# RxFrontendWaveyRadar.net
KiCad netlist of a schematic drawn in Altium Designer
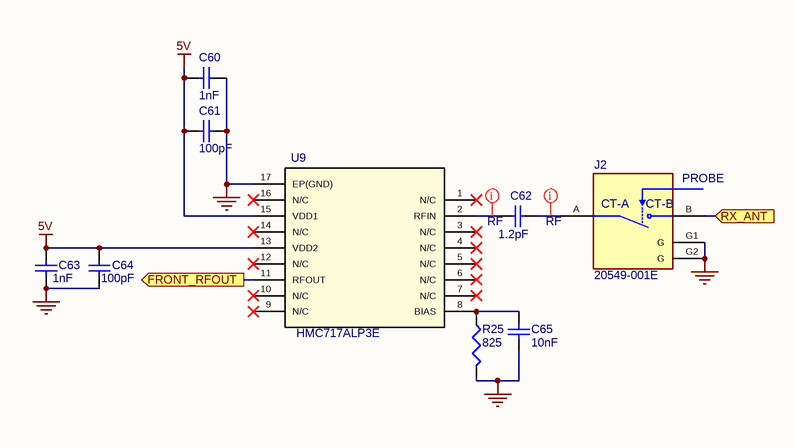
[diagram p0: RxFrontendWaveyRadar.SchDoc]

(export (version "E")
  (design (tool "Eeschema 10.0.6"))
  (components
    (comp (ref "C60")
      (value "1nF")
      (footprint "CAPC0402(1005)33_L")
      (description "Chip Capacitor, 1nF +/-20%, 50V, 0402, Thickness 0.33 mm")
      (fields (field (name "TOLERANCE") "10%") (field (name "Comment") "Capacitor 1nF +/-20% 50V 0402"))
      (libsource (lib "University of South Florida") (part "CAP-NP-2"))
    )
    (comp (ref "C61")
      (value "100pF")
      (footprint "CAPC1005X56X25LL10T15")
      (fields (field (name "Comment") "04023A101JAT2A"))
      (libsource (lib "University of South Florida") (part "CAP-NP-2"))
    )
    (comp (ref "C62")
      (value "1.2pF")
      (footprint "FP-C0402-BB-MFG")
      (description "Cap Ceramic 1.2pF 50V C0G 0.25pF SMD 0402 125°C Paper T/R")
      (fields (field (name "Comment") "C0402C129C5GACTU"))
      (libsource (lib "University of South Florida") (part "CAP-NP-2"))
    )
    (comp (ref "C63")
      (value "1nF")
      (footprint "CAPC0402(1005)33_L")
      (description "Chip Capacitor, 1nF +/-20%, 50V, 0402, Thickness 0.33 mm")
      (fields (field (name "TOLERANCE") "10%") (field (name "Comment") "Capacitor 1nF +/-20% 50V 0402"))
      (libsource (lib "University of South Florida") (part "CAP-NP-2"))
    )
    (comp (ref "C64")
      (value "100pF")
      (footprint "CAPC1005X56X25LL10T15")
      (fields (field (name "Comment") "04023A101JAT2A"))
      (libsource (lib "University of South Florida") (part "CAP-NP-2"))
    )
    (comp (ref "C65")
      (value "10nF")
      (footprint "CAPC0402(1005)60_L")
      (description "Chip Capacitor, 10nF +/-20%, 50V, 0402, Thickness 0.6 mm")
      (fields (field (name "TOLERANCE") "5%") (field (name "Comment") "Capacitor 10nF +/-20% 50V 0402"))
      (libsource (lib "University of South Florida") (part "CAP-NP-2"))
    )
    (comp (ref "J2")
      (value "20549-001E")
      (footprint "IPEX_20549-001E")
      (fields (field (name "MF") "I-PEX"))
      (libsource (lib "University of South Florida") (part "20549-001E"))
    )
    (comp (ref "R25")
      (value "825")
      (footprint "RESC1005X40X25NL05T05")
      (description "Resistor;  Thick Film;  825 Ohms;  0.063 W;  1%;  SMT;  0402;  TCR 37 ppm/DegC;  Cut Tape")
      (fields (field (name "Comment") "CRCW0402825RFKED"))
      (libsource (lib "University of South Florida") (part "ResistorSymbol"))
    )
    (comp (ref "U9")
      (value "HMC717ALP3E")
      (footprint "HCP_16_3")
      (description "No Description Available")
      (fields (field (name "COPYRIGHT") "Copyright (C) 2018 Accelerated Designs. All rights reserved"))
      (libsource (lib "University of South Florida") (part "HMC717ALP3E"))
    )
  )
  (nets
    (net (code "1") (name "/FRONT_RFOUT") (class "Default")
      (node (ref "U9") (pin "11") (pinfunction "RFOUT_11") (pintype "passive"))
    )
    (net (code "2") (name "/RX_ANT") (class "Default")
      (node (ref "J2") (pin "B") (pinfunction "CT-B_B") (pintype "passive"))
    )
    (net (code "3") (name "5V") (class "Default")
      (node (ref "C60") (pin "2") (pinfunction "2_2") (pintype "passive"))
      (node (ref "C61") (pin "2") (pinfunction "2_2") (pintype "passive"))
      (node (ref "C63") (pin "2") (pinfunction "2_2") (pintype "passive"))
      (node (ref "C64") (pin "2") (pinfunction "2_2") (pintype "passive"))
      (node (ref "U9") (pin "13") (pinfunction "VDD2_13") (pintype "passive"))
      (node (ref "U9") (pin "15") (pinfunction "VDD1_15") (pintype "passive"))
    )
    (net (code "4") (name "GND") (class "Default")
      (node (ref "C60") (pin "1") (pinfunction "1_1") (pintype "passive"))
      (node (ref "C61") (pin "1") (pinfunction "1_1") (pintype "passive"))
      (node (ref "C63") (pin "1") (pinfunction "1_1") (pintype "passive"))
      (node (ref "C64") (pin "1") (pinfunction "1_1") (pintype "passive"))
      (node (ref "C65") (pin "2") (pinfunction "2_2") (pintype "passive"))
      (node (ref "J2") (pin "G1") (pinfunction "G_G1") (pintype "power_in"))
      (node (ref "J2") (pin "G2") (pinfunction "G_G2") (pintype "power_in"))
      (node (ref "R25") (pin "2") (pinfunction "2_2") (pintype "passive"))
      (node (ref "U9") (pin "17") (pinfunction "EP(GND)_17") (pintype "passive"))
    )
    (net (code "5") (name "Net-(J2-CT-A)") (class "Default")
      (node (ref "C62") (pin "2") (pinfunction "2_2") (pintype "passive"))
      (node (ref "J2") (pin "A") (pinfunction "CT-A_A") (pintype "passive"))
    )
    (net (code "6") (name "Net-(U9-BIAS)") (class "Default")
      (node (ref "C65") (pin "1") (pinfunction "1_1") (pintype "passive"))
      (node (ref "R25") (pin "1") (pinfunction "1_1") (pintype "passive"))
      (node (ref "U9") (pin "8") (pinfunction "BIAS_8") (pintype "passive"))
    )
    (net (code "7") (name "Net-(U9-RFIN)") (class "Default")
      (node (ref "C62") (pin "1") (pinfunction "1_1") (pintype "passive"))
      (node (ref "U9") (pin "2") (pinfunction "RFIN_2") (pintype "passive"))
    )
    (net (code "8") (name "unconnected-(U9-N{slash}C-Pad1)") (class "Default")
      (node (ref "U9") (pin "1") (pinfunction "N/C_1") (pintype "passive+no_connect"))
    )
    (net (code "9") (name "unconnected-(U9-N{slash}C-Pad3)") (class "Default")
      (node (ref "U9") (pin "3") (pinfunction "N/C_3") (pintype "passive+no_connect"))
    )
    (net (code "10") (name "unconnected-(U9-N{slash}C-Pad4)") (class "Default")
      (node (ref "U9") (pin "4") (pinfunction "N/C_4") (pintype "passive+no_connect"))
    )
    (net (code "11") (name "unconnected-(U9-N{slash}C-Pad5)") (class "Default")
      (node (ref "U9") (pin "5") (pinfunction "N/C_5") (pintype "passive+no_connect"))
    )
    (net (code "12") (name "unconnected-(U9-N{slash}C-Pad6)") (class "Default")
      (node (ref "U9") (pin "6") (pinfunction "N/C_6") (pintype "passive+no_connect"))
    )
    (net (code "13") (name "unconnected-(U9-N{slash}C-Pad7)") (class "Default")
      (node (ref "U9") (pin "7") (pinfunction "N/C_7") (pintype "passive+no_connect"))
    )
    (net (code "14") (name "unconnected-(U9-N{slash}C-Pad9)") (class "Default")
      (node (ref "U9") (pin "9") (pinfunction "N/C_9") (pintype "passive+no_connect"))
    )
    (net (code "15") (name "unconnected-(U9-N{slash}C-Pad10)") (class "Default")
      (node (ref "U9") (pin "10") (pinfunction "N/C_10") (pintype "passive+no_connect"))
    )
    (net (code "16") (name "unconnected-(U9-N{slash}C-Pad12)") (class "Default")
      (node (ref "U9") (pin "12") (pinfunction "N/C_12") (pintype "passive+no_connect"))
    )
    (net (code "17") (name "unconnected-(U9-N{slash}C-Pad14)") (class "Default")
      (node (ref "U9") (pin "14") (pinfunction "N/C_14") (pintype "passive+no_connect"))
    )
    (net (code "18") (name "unconnected-(U9-N{slash}C-Pad16)") (class "Default")
      (node (ref "U9") (pin "16") (pinfunction "N/C_16") (pintype "passive+no_connect"))
    )
  )
)
